# RP2040.net
KiCad netlist of a schematic drawn in Altium Designer
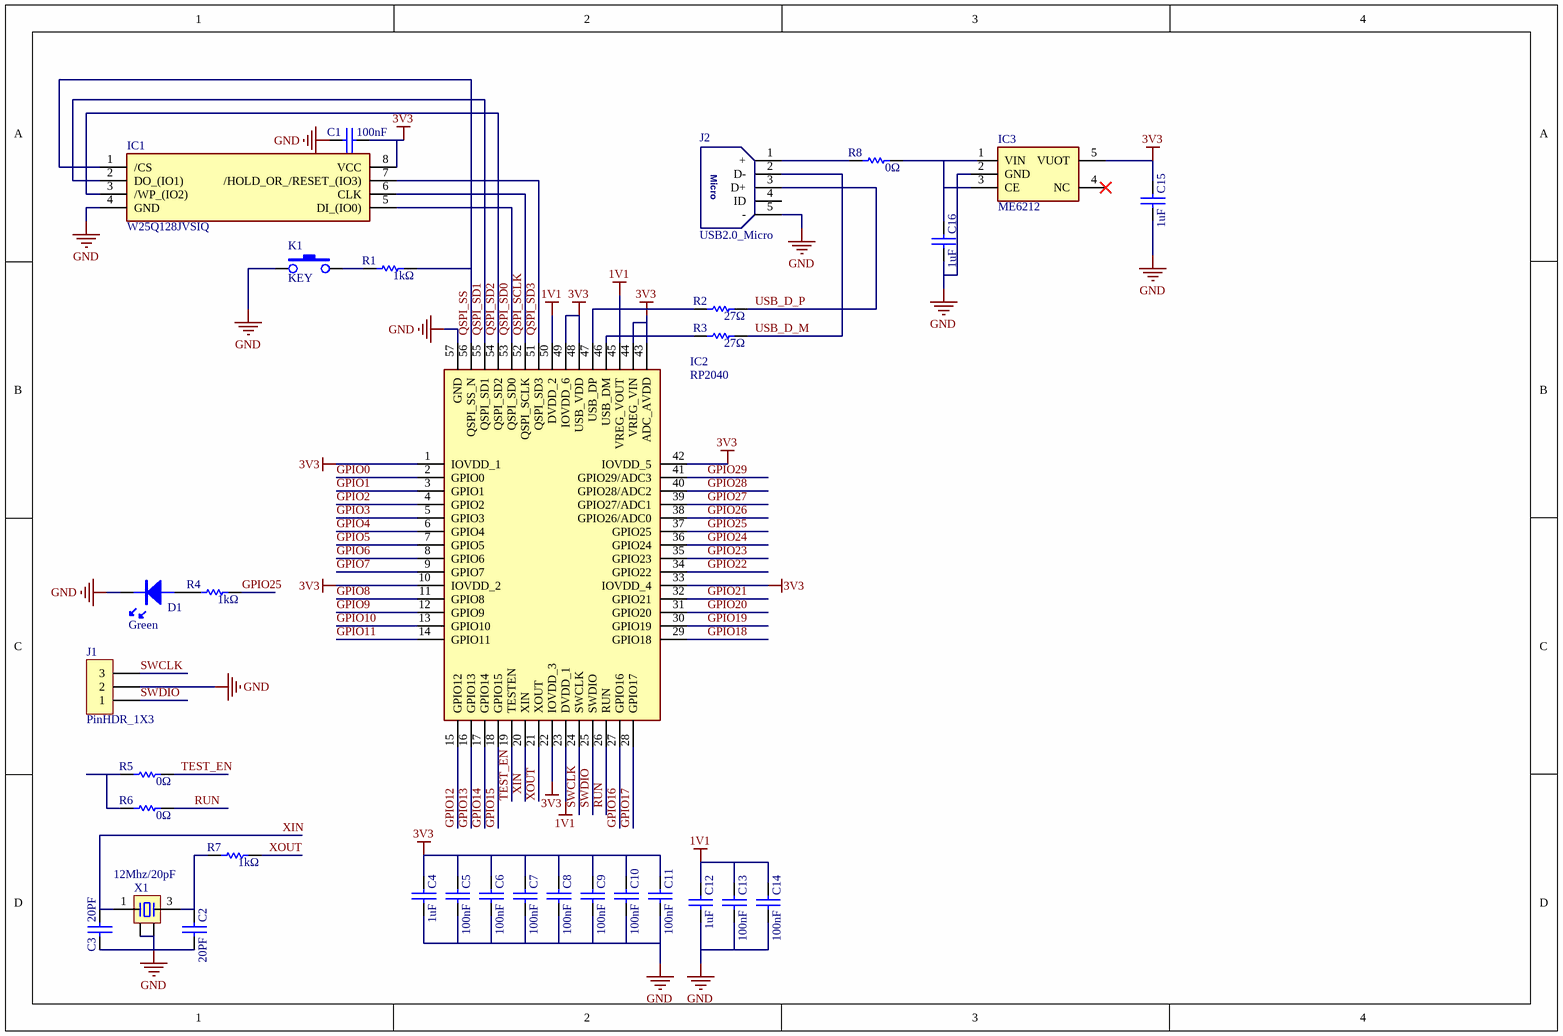
[diagram p0: RP2040.SchDoc]

(export (version "E")
  (design (tool "Eeschema 10.0.6"))
  (components
    (comp (ref "C1")
      (value "100nF")
      (footprint "C_0402")
      (description "贴片电容")
      (libsource (lib "IntLib-Passive") (part "Cap_Chip"))
    )
    (comp (ref "C2")
      (value "20PF")
      (footprint "C_0402")
      (description "贴片电容")
      (libsource (lib "IntLib-Passive") (part "Cap_Chip"))
    )
    (comp (ref "C3")
      (value "20PF")
      (footprint "C_0402")
      (description "贴片电容")
      (libsource (lib "IntLib-Passive") (part "Cap_Chip"))
    )
    (comp (ref "C4")
      (value "1uF")
      (footprint "C_0402")
      (description "贴片电容")
      (libsource (lib "IntLib-Passive") (part "Cap_Chip"))
    )
    (comp (ref "C5")
      (value "100nF")
      (footprint "C_0402")
      (description "贴片电容")
      (libsource (lib "IntLib-Passive") (part "Cap_Chip"))
    )
    (comp (ref "C6")
      (value "100nF")
      (footprint "C_0402")
      (description "贴片电容")
      (libsource (lib "IntLib-Passive") (part "Cap_Chip"))
    )
    (comp (ref "C7")
      (value "100nF")
      (footprint "C_0402")
      (description "贴片电容")
      (libsource (lib "IntLib-Passive") (part "Cap_Chip"))
    )
    (comp (ref "C8")
      (value "100nF")
      (footprint "C_0402")
      (description "贴片电容")
      (libsource (lib "IntLib-Passive") (part "Cap_Chip"))
    )
    (comp (ref "C9")
      (value "100nF")
      (footprint "C_0402")
      (description "贴片电容")
      (libsource (lib "IntLib-Passive") (part "Cap_Chip"))
    )
    (comp (ref "C10")
      (value "100nF")
      (footprint "C_0402")
      (description "贴片电容")
      (libsource (lib "IntLib-Passive") (part "Cap_Chip"))
    )
    (comp (ref "C11")
      (value "100nF")
      (footprint "C_0402")
      (description "贴片电容")
      (libsource (lib "IntLib-Passive") (part "Cap_Chip"))
    )
    (comp (ref "C12")
      (value "1uF")
      (footprint "C_0402")
      (description "贴片电容")
      (libsource (lib "IntLib-Passive") (part "Cap_Chip"))
    )
    (comp (ref "C13")
      (value "100nF")
      (footprint "C_0402")
      (description "贴片电容")
      (libsource (lib "IntLib-Passive") (part "Cap_Chip"))
    )
    (comp (ref "C14")
      (value "100nF")
      (footprint "C_0402")
      (description "贴片电容")
      (libsource (lib "IntLib-Passive") (part "Cap_Chip"))
    )
    (comp (ref "C15")
      (value "1uF")
      (footprint "C_0402")
      (description "贴片电容")
      (libsource (lib "IntLib-Passive") (part "Cap_Chip"))
    )
    (comp (ref "C16")
      (value "1uF")
      (footprint "C_0402")
      (description "贴片电容")
      (libsource (lib "IntLib-Passive") (part "Cap_Chip"))
    )
    (comp (ref "D1")
      (value "Green")
      (footprint "LED-0603-G")
      (description "贴片LED")
      (libsource (lib "IntLib-Active") (part "LED_Chip"))
    )
    (comp (ref "IC1")
      (value "W25Q128JVSIQ")
      (footprint "SamacSys:SOIC127P790X216-8N")
      (description "Integrated Circuit")
      (fields (field (name "MOUSER PART NUMBER") "454-W25Q128JVSIQ"))
      (libsource (lib "*") (part "W25Q128JVSIQ"))
    )
    (comp (ref "IC2")
      (value "RP2040")
      (footprint "SamacSys:QFN40P700X700X90-57N-D")
      (description "Integrated Circuit")
      (libsource (lib "*") (part "RP2040"))
    )
    (comp (ref "IC3")
      (value "ME6212")
      (footprint "SOT23-5")
      (description "LDO 线性稳压芯片")
      (libsource (lib "IntLib-IC") (part "ME6212"))
    )
    (comp (ref "J1")
      (value "PinHDR_1X3")
      (footprint "Pin HDR1X3/2.54mm-S")
      (libsource (lib "IntLib-Connector") (part "PinHDR_1X3"))
    )
    (comp (ref "J2")
      (value "USB2.0_Micro")
      (footprint "USB-micro_B")
      (description "MicroUSB 2.0连接座")
      (libsource (lib "IntLib-Connector") (part "USB2.0_Micro"))
    )
    (comp (ref "K1")
      (value "KEY")
      (footprint "SMD-3X6X4.3")
      (description "轻触开关")
      (libsource (lib "IntLib-Switch") (part "KEY"))
    )
    (comp (ref "R1")
      (value "1kΩ")
      (footprint "R_0402")
      (description "贴片电阻")
      (libsource (lib "IntLib-Passive") (part "Res_Chip"))
    )
    (comp (ref "R2")
      (value "27Ω")
      (footprint "R_0402")
      (description "贴片电阻")
      (libsource (lib "IntLib-Passive") (part "Res_Chip"))
    )
    (comp (ref "R3")
      (value "27Ω")
      (footprint "R_0402")
      (description "贴片电阻")
      (libsource (lib "IntLib-Passive") (part "Res_Chip"))
    )
    (comp (ref "R4")
      (value "1kΩ")
      (footprint "R_0402")
      (description "贴片电阻")
      (libsource (lib "IntLib-Passive") (part "Res_Chip"))
    )
    (comp (ref "R5")
      (value "0Ω")
      (footprint "R_0402")
      (description "贴片电阻")
      (libsource (lib "IntLib-Passive") (part "Res_Chip"))
    )
    (comp (ref "R6")
      (value "0Ω")
      (footprint "R_0402")
      (description "贴片电阻")
      (libsource (lib "IntLib-Passive") (part "Res_Chip"))
    )
    (comp (ref "R7")
      (value "1kΩ")
      (footprint "R_0402")
      (description "贴片电阻")
      (libsource (lib "IntLib-Passive") (part "Res_Chip"))
    )
    (comp (ref "R8")
      (value "0Ω")
      (footprint "R_0402")
      (description "贴片电阻")
      (libsource (lib "IntLib-Passive") (part "Res_Chip"))
    )
    (comp (ref "X1")
      (value "12Mhz/20pF")
      (footprint "XTAL_3225-4P")
      (description "4脚无源晶振")
      (fields (field (name "MANUFACTURER_PART_NUMBER") "X322512MSB4SI"))
      (libsource (lib "IntLib-Active") (part "Crystal_4P"))
    )
  )
  (nets
    (net (code "1") (name "/GPIO0") (class "Default")
      (node (ref "IC2") (pin "2") (pinfunction "GPIO0_2") (pintype "passive"))
    )
    (net (code "2") (name "/GPIO1") (class "Default")
      (node (ref "IC2") (pin "3") (pinfunction "GPIO1_3") (pintype "passive"))
    )
    (net (code "3") (name "/GPIO2") (class "Default")
      (node (ref "IC2") (pin "4") (pinfunction "GPIO2_4") (pintype "passive"))
    )
    (net (code "4") (name "/GPIO3") (class "Default")
      (node (ref "IC2") (pin "5") (pinfunction "GPIO3_5") (pintype "passive"))
    )
    (net (code "5") (name "/GPIO4") (class "Default")
      (node (ref "IC2") (pin "6") (pinfunction "GPIO4_6") (pintype "passive"))
    )
    (net (code "6") (name "/GPIO5") (class "Default")
      (node (ref "IC2") (pin "7") (pinfunction "GPIO5_7") (pintype "passive"))
    )
    (net (code "7") (name "/GPIO6") (class "Default")
      (node (ref "IC2") (pin "8") (pinfunction "GPIO6_8") (pintype "passive"))
    )
    (net (code "8") (name "/GPIO7") (class "Default")
      (node (ref "IC2") (pin "9") (pinfunction "GPIO7_9") (pintype "passive"))
    )
    (net (code "9") (name "/GPIO8") (class "Default")
      (node (ref "IC2") (pin "11") (pinfunction "GPIO8_11") (pintype "passive"))
    )
    (net (code "10") (name "/GPIO9") (class "Default")
      (node (ref "IC2") (pin "12") (pinfunction "GPIO9_12") (pintype "passive"))
    )
    (net (code "11") (name "/GPIO10") (class "Default")
      (node (ref "IC2") (pin "13") (pinfunction "GPIO10_13") (pintype "passive"))
    )
    (net (code "12") (name "/GPIO11") (class "Default")
      (node (ref "IC2") (pin "14") (pinfunction "GPIO11_14") (pintype "passive"))
    )
    (net (code "13") (name "/GPIO12") (class "Default")
      (node (ref "IC2") (pin "15") (pinfunction "GPIO12_15") (pintype "passive"))
    )
    (net (code "14") (name "/GPIO13") (class "Default")
      (node (ref "IC2") (pin "16") (pinfunction "GPIO13_16") (pintype "passive"))
    )
    (net (code "15") (name "/GPIO14") (class "Default")
      (node (ref "IC2") (pin "17") (pinfunction "GPIO14_17") (pintype "passive"))
    )
    (net (code "16") (name "/GPIO15") (class "Default")
      (node (ref "IC2") (pin "18") (pinfunction "GPIO15_18") (pintype "passive"))
    )
    (net (code "17") (name "/GPIO16") (class "Default")
      (node (ref "IC2") (pin "27") (pinfunction "GPIO16_27") (pintype "passive"))
    )
    (net (code "18") (name "/GPIO17") (class "Default")
      (node (ref "IC2") (pin "28") (pinfunction "GPIO17_28") (pintype "passive"))
    )
    (net (code "19") (name "/GPIO18") (class "Default")
      (node (ref "IC2") (pin "29") (pinfunction "GPIO18_29") (pintype "passive"))
    )
    (net (code "20") (name "/GPIO19") (class "Default")
      (node (ref "IC2") (pin "30") (pinfunction "GPIO19_30") (pintype "passive"))
    )
    (net (code "21") (name "/GPIO20") (class "Default")
      (node (ref "IC2") (pin "31") (pinfunction "GPIO20_31") (pintype "passive"))
    )
    (net (code "22") (name "/GPIO21") (class "Default")
      (node (ref "IC2") (pin "32") (pinfunction "GPIO21_32") (pintype "passive"))
    )
    (net (code "23") (name "/GPIO22") (class "Default")
      (node (ref "IC2") (pin "34") (pinfunction "GPIO22_34") (pintype "passive"))
    )
    (net (code "24") (name "/GPIO23") (class "Default")
      (node (ref "IC2") (pin "35") (pinfunction "GPIO23_35") (pintype "passive"))
    )
    (net (code "25") (name "/GPIO24") (class "Default")
      (node (ref "IC2") (pin "36") (pinfunction "GPIO24_36") (pintype "passive"))
    )
    (net (code "26") (name "/GPIO25") (class "Default")
      (node (ref "IC2") (pin "37") (pinfunction "GPIO25_37") (pintype "passive"))
      (node (ref "R4") (pin "2") (pinfunction "2_2") (pintype "passive"))
    )
    (net (code "27") (name "/GPIO26") (class "Default")
      (node (ref "IC2") (pin "38") (pinfunction "GPIO26/ADC0_38") (pintype "passive"))
    )
    (net (code "28") (name "/GPIO27") (class "Default")
      (node (ref "IC2") (pin "39") (pinfunction "GPIO27/ADC1_39") (pintype "passive"))
    )
    (net (code "29") (name "/GPIO28") (class "Default")
      (node (ref "IC2") (pin "40") (pinfunction "GPIO28/ADC2_40") (pintype "passive"))
    )
    (net (code "30") (name "/GPIO29") (class "Default")
      (node (ref "IC2") (pin "41") (pinfunction "GPIO29/ADC3_41") (pintype "passive"))
    )
    (net (code "31") (name "/QSPI_SCLK") (class "Default")
      (node (ref "IC1") (pin "6") (pinfunction "CLK_6") (pintype "passive"))
      (node (ref "IC2") (pin "52") (pinfunction "QSPI_SCLK_52") (pintype "passive"))
    )
    (net (code "32") (name "/QSPI_SD0") (class "Default")
      (node (ref "IC1") (pin "5") (pinfunction "DI_(IO0)_5") (pintype "passive"))
      (node (ref "IC2") (pin "53") (pinfunction "QSPI_SD0_53") (pintype "passive"))
    )
    (net (code "33") (name "/QSPI_SD1") (class "Default")
      (node (ref "IC1") (pin "2") (pinfunction "DO_(IO1)_2") (pintype "passive"))
      (node (ref "IC2") (pin "55") (pinfunction "QSPI_SD1_55") (pintype "passive"))
    )
    (net (code "34") (name "/QSPI_SD2") (class "Default")
      (node (ref "IC1") (pin "3") (pinfunction "/WP_(IO2)_3") (pintype "passive"))
      (node (ref "IC2") (pin "54") (pinfunction "QSPI_SD2_54") (pintype "passive"))
    )
    (net (code "35") (name "/QSPI_SD3") (class "Default")
      (node (ref "IC1") (pin "7") (pinfunction "/HOLD_OR_/RESET_(IO3)_7") (pintype "passive"))
      (node (ref "IC2") (pin "51") (pinfunction "QSPI_SD3_51") (pintype "passive"))
    )
    (net (code "36") (name "/QSPI_SS") (class "Default")
      (node (ref "IC1") (pin "1") (pinfunction "/CS_1") (pintype "passive"))
      (node (ref "IC2") (pin "56") (pinfunction "QSPI_SS_N_56") (pintype "passive"))
      (node (ref "R1") (pin "2") (pinfunction "2_2") (pintype "passive"))
    )
    (net (code "37") (name "/RUN") (class "Default")
      (node (ref "IC2") (pin "26") (pinfunction "RUN_26") (pintype "passive"))
      (node (ref "R6") (pin "2") (pinfunction "2_2") (pintype "passive"))
    )
    (net (code "38") (name "/SWCLK") (class "Default")
      (node (ref "IC2") (pin "24") (pinfunction "SWCLK_24") (pintype "passive"))
      (node (ref "J1") (pin "3") (pinfunction "3_3") (pintype "passive"))
    )
    (net (code "39") (name "/SWDIO") (class "Default")
      (node (ref "IC2") (pin "25") (pinfunction "SWDIO_25") (pintype "passive"))
      (node (ref "J1") (pin "1") (pinfunction "1_1") (pintype "passive"))
    )
    (net (code "40") (name "/TEST_EN") (class "Default")
      (node (ref "IC2") (pin "19") (pinfunction "TESTEN_19") (pintype "passive"))
      (node (ref "R5") (pin "2") (pinfunction "2_2") (pintype "passive"))
    )
    (net (code "41") (name "/USB_D_M") (class "Default")
      (node (ref "J2") (pin "2") (pinfunction "D-_2") (pintype "passive"))
      (node (ref "R3") (pin "2") (pinfunction "2_2") (pintype "passive"))
    )
    (net (code "42") (name "/USB_D_P") (class "Default")
      (node (ref "J2") (pin "3") (pinfunction "D+_3") (pintype "passive"))
      (node (ref "R2") (pin "2") (pinfunction "2_2") (pintype "passive"))
    )
    (net (code "43") (name "/XIN") (class "Default")
      (node (ref "C3") (pin "2") (pinfunction "2_2") (pintype "passive"))
      (node (ref "IC2") (pin "20") (pinfunction "XIN_20") (pintype "passive"))
      (node (ref "X1") (pin "1") (pinfunction "1_1") (pintype "passive"))
    )
    (net (code "44") (name "/XOUT") (class "Default")
      (node (ref "IC2") (pin "21") (pinfunction "XOUT_21") (pintype "passive"))
      (node (ref "R7") (pin "2") (pinfunction "2_2") (pintype "passive"))
    )
    (net (code "45") (name "1V1") (class "Default")
      (node (ref "C12") (pin "1") (pinfunction "1_1") (pintype "passive"))
      (node (ref "C13") (pin "1") (pinfunction "1_1") (pintype "passive"))
      (node (ref "C14") (pin "1") (pinfunction "1_1") (pintype "passive"))
      (node (ref "IC2") (pin "23") (pinfunction "DVDD_1_23") (pintype "passive"))
      (node (ref "IC2") (pin "45") (pinfunction "VREG_VOUT_45") (pintype "passive"))
      (node (ref "IC2") (pin "50") (pinfunction "DVDD_2_50") (pintype "passive"))
    )
    (net (code "46") (name "3V3") (class "Default")
      (node (ref "C1") (pin "2") (pinfunction "2_2") (pintype "passive"))
      (node (ref "C10") (pin "1") (pinfunction "1_1") (pintype "passive"))
      (node (ref "C11") (pin "1") (pinfunction "1_1") (pintype "passive"))
      (node (ref "C15") (pin "1") (pinfunction "1_1") (pintype "passive"))
      (node (ref "C4") (pin "1") (pinfunction "1_1") (pintype "passive"))
      (node (ref "C5") (pin "1") (pinfunction "1_1") (pintype "passive"))
      (node (ref "C6") (pin "1") (pinfunction "1_1") (pintype "passive"))
      (node (ref "C7") (pin "1") (pinfunction "1_1") (pintype "passive"))
      (node (ref "C8") (pin "1") (pinfunction "1_1") (pintype "passive"))
      (node (ref "C9") (pin "1") (pinfunction "1_1") (pintype "passive"))
      (node (ref "IC1") (pin "8") (pinfunction "VCC_8") (pintype "passive"))
      (node (ref "IC2") (pin "1") (pinfunction "IOVDD_1_1") (pintype "passive"))
      (node (ref "IC2") (pin "10") (pinfunction "IOVDD_2_10") (pintype "passive"))
      (node (ref "IC2") (pin "22") (pinfunction "IOVDD_3_22") (pintype "passive"))
      (node (ref "IC2") (pin "33") (pinfunction "IOVDD_4_33") (pintype "passive"))
      (node (ref "IC2") (pin "42") (pinfunction "IOVDD_5_42") (pintype "passive"))
      (node (ref "IC2") (pin "43") (pinfunction "ADC_AVDD_43") (pintype "passive"))
      (node (ref "IC2") (pin "44") (pinfunction "VREG_VIN_44") (pintype "passive"))
      (node (ref "IC2") (pin "48") (pinfunction "USB_VDD_48") (pintype "passive"))
      (node (ref "IC2") (pin "49") (pinfunction "IOVDD_6_49") (pintype "passive"))
      (node (ref "IC3") (pin "5") (pinfunction "VUOT_5") (pintype "passive"))
    )
    (net (code "47") (name "GND") (class "Default")
      (node (ref "C1") (pin "1") (pinfunction "1_1") (pintype "passive"))
      (node (ref "C10") (pin "2") (pinfunction "2_2") (pintype "passive"))
      (node (ref "C11") (pin "2") (pinfunction "2_2") (pintype "passive"))
      (node (ref "C12") (pin "2") (pinfunction "2_2") (pintype "passive"))
      (node (ref "C13") (pin "2") (pinfunction "2_2") (pintype "passive"))
      (node (ref "C14") (pin "2") (pinfunction "2_2") (pintype "passive"))
      (node (ref "C15") (pin "2") (pinfunction "2_2") (pintype "passive"))
      (node (ref "C16") (pin "2") (pinfunction "2_2") (pintype "passive"))
      (node (ref "C2") (pin "2") (pinfunction "2_2") (pintype "passive"))
      (node (ref "C3") (pin "1") (pinfunction "1_1") (pintype "passive"))
      (node (ref "C4") (pin "2") (pinfunction "2_2") (pintype "passive"))
      (node (ref "C5") (pin "2") (pinfunction "2_2") (pintype "passive"))
      (node (ref "C6") (pin "2") (pinfunction "2_2") (pintype "passive"))
      (node (ref "C7") (pin "2") (pinfunction "2_2") (pintype "passive"))
      (node (ref "C8") (pin "2") (pinfunction "2_2") (pintype "passive"))
      (node (ref "C9") (pin "2") (pinfunction "2_2") (pintype "passive"))
      (node (ref "D1") (pin "K") (pinfunction "K_K") (pintype "passive"))
      (node (ref "IC1") (pin "4") (pinfunction "GND_4") (pintype "passive"))
      (node (ref "IC2") (pin "57") (pinfunction "GND_57") (pintype "passive"))
      (node (ref "IC3") (pin "2") (pinfunction "GND_2") (pintype "passive"))
      (node (ref "J1") (pin "2") (pinfunction "2_2") (pintype "passive"))
      (node (ref "J2") (pin "5") (pinfunction "-_5") (pintype "passive"))
      (node (ref "K1") (pin "1") (pinfunction "1_1") (pintype "passive"))
      (node (ref "X1") (pin "2") (pinfunction "2_2") (pintype "passive"))
      (node (ref "X1") (pin "4") (pinfunction "4_4") (pintype "passive"))
    )
    (net (code "48") (name "Net-(C2-Pad1)") (class "Default")
      (node (ref "C2") (pin "1") (pinfunction "1_1") (pintype "passive"))
      (node (ref "R7") (pin "1") (pinfunction "1_1") (pintype "passive"))
      (node (ref "X1") (pin "3") (pinfunction "3_3") (pintype "passive"))
    )
    (net (code "49") (name "Net-(D1-PadA)") (class "Default")
      (node (ref "D1") (pin "A") (pinfunction "A_A") (pintype "passive"))
      (node (ref "R4") (pin "1") (pinfunction "1_1") (pintype "passive"))
    )
    (net (code "50") (name "Net-(IC2-USB_DM)") (class "Default")
      (node (ref "IC2") (pin "46") (pinfunction "USB_DM_46") (pintype "passive"))
      (node (ref "R3") (pin "1") (pinfunction "1_1") (pintype "passive"))
    )
    (net (code "51") (name "Net-(IC2-USB_DP)") (class "Default")
      (node (ref "IC2") (pin "47") (pinfunction "USB_DP_47") (pintype "passive"))
      (node (ref "R2") (pin "1") (pinfunction "1_1") (pintype "passive"))
    )
    (net (code "52") (name "Net-(IC3-CE)") (class "Default")
      (node (ref "C16") (pin "1") (pinfunction "1_1") (pintype "passive"))
      (node (ref "IC3") (pin "1") (pinfunction "VIN_1") (pintype "passive"))
      (node (ref "IC3") (pin "3") (pinfunction "CE_3") (pintype "passive"))
      (node (ref "R8") (pin "2") (pinfunction "2_2") (pintype "passive"))
    )
    (net (code "53") (name "Net-(J2-+)") (class "Default")
      (node (ref "J2") (pin "1") (pinfunction "+_1") (pintype "passive"))
      (node (ref "R8") (pin "1") (pinfunction "1_1") (pintype "passive"))
    )
    (net (code "54") (name "Net-(K1-Pad3)") (class "Default")
      (node (ref "K1") (pin "3") (pinfunction "3_3") (pintype "passive"))
      (node (ref "R1") (pin "1") (pinfunction "1_1") (pintype "passive"))
    )
    (net (code "55") (name "Net-(R5-Pad1)") (class "Default")
      (node (ref "R5") (pin "1") (pinfunction "1_1") (pintype "passive"))
      (node (ref "R6") (pin "1") (pinfunction "1_1") (pintype "passive"))
    )
    (net (code "56") (name "unconnected-(IC3-NC-Pad4)") (class "Default")
      (node (ref "IC3") (pin "4") (pinfunction "NC_4") (pintype "passive+no_connect"))
    )
    (net (code "57") (name "unconnected-(J2-ID-Pad4)") (class "Default")
      (node (ref "J2") (pin "4") (pinfunction "ID_4") (pintype "passive"))
    )
  )
)
